# SCH_FG_Command_Controller_2021-10-20.net
KiCad netlist of a schematic drawn in EasyEDA
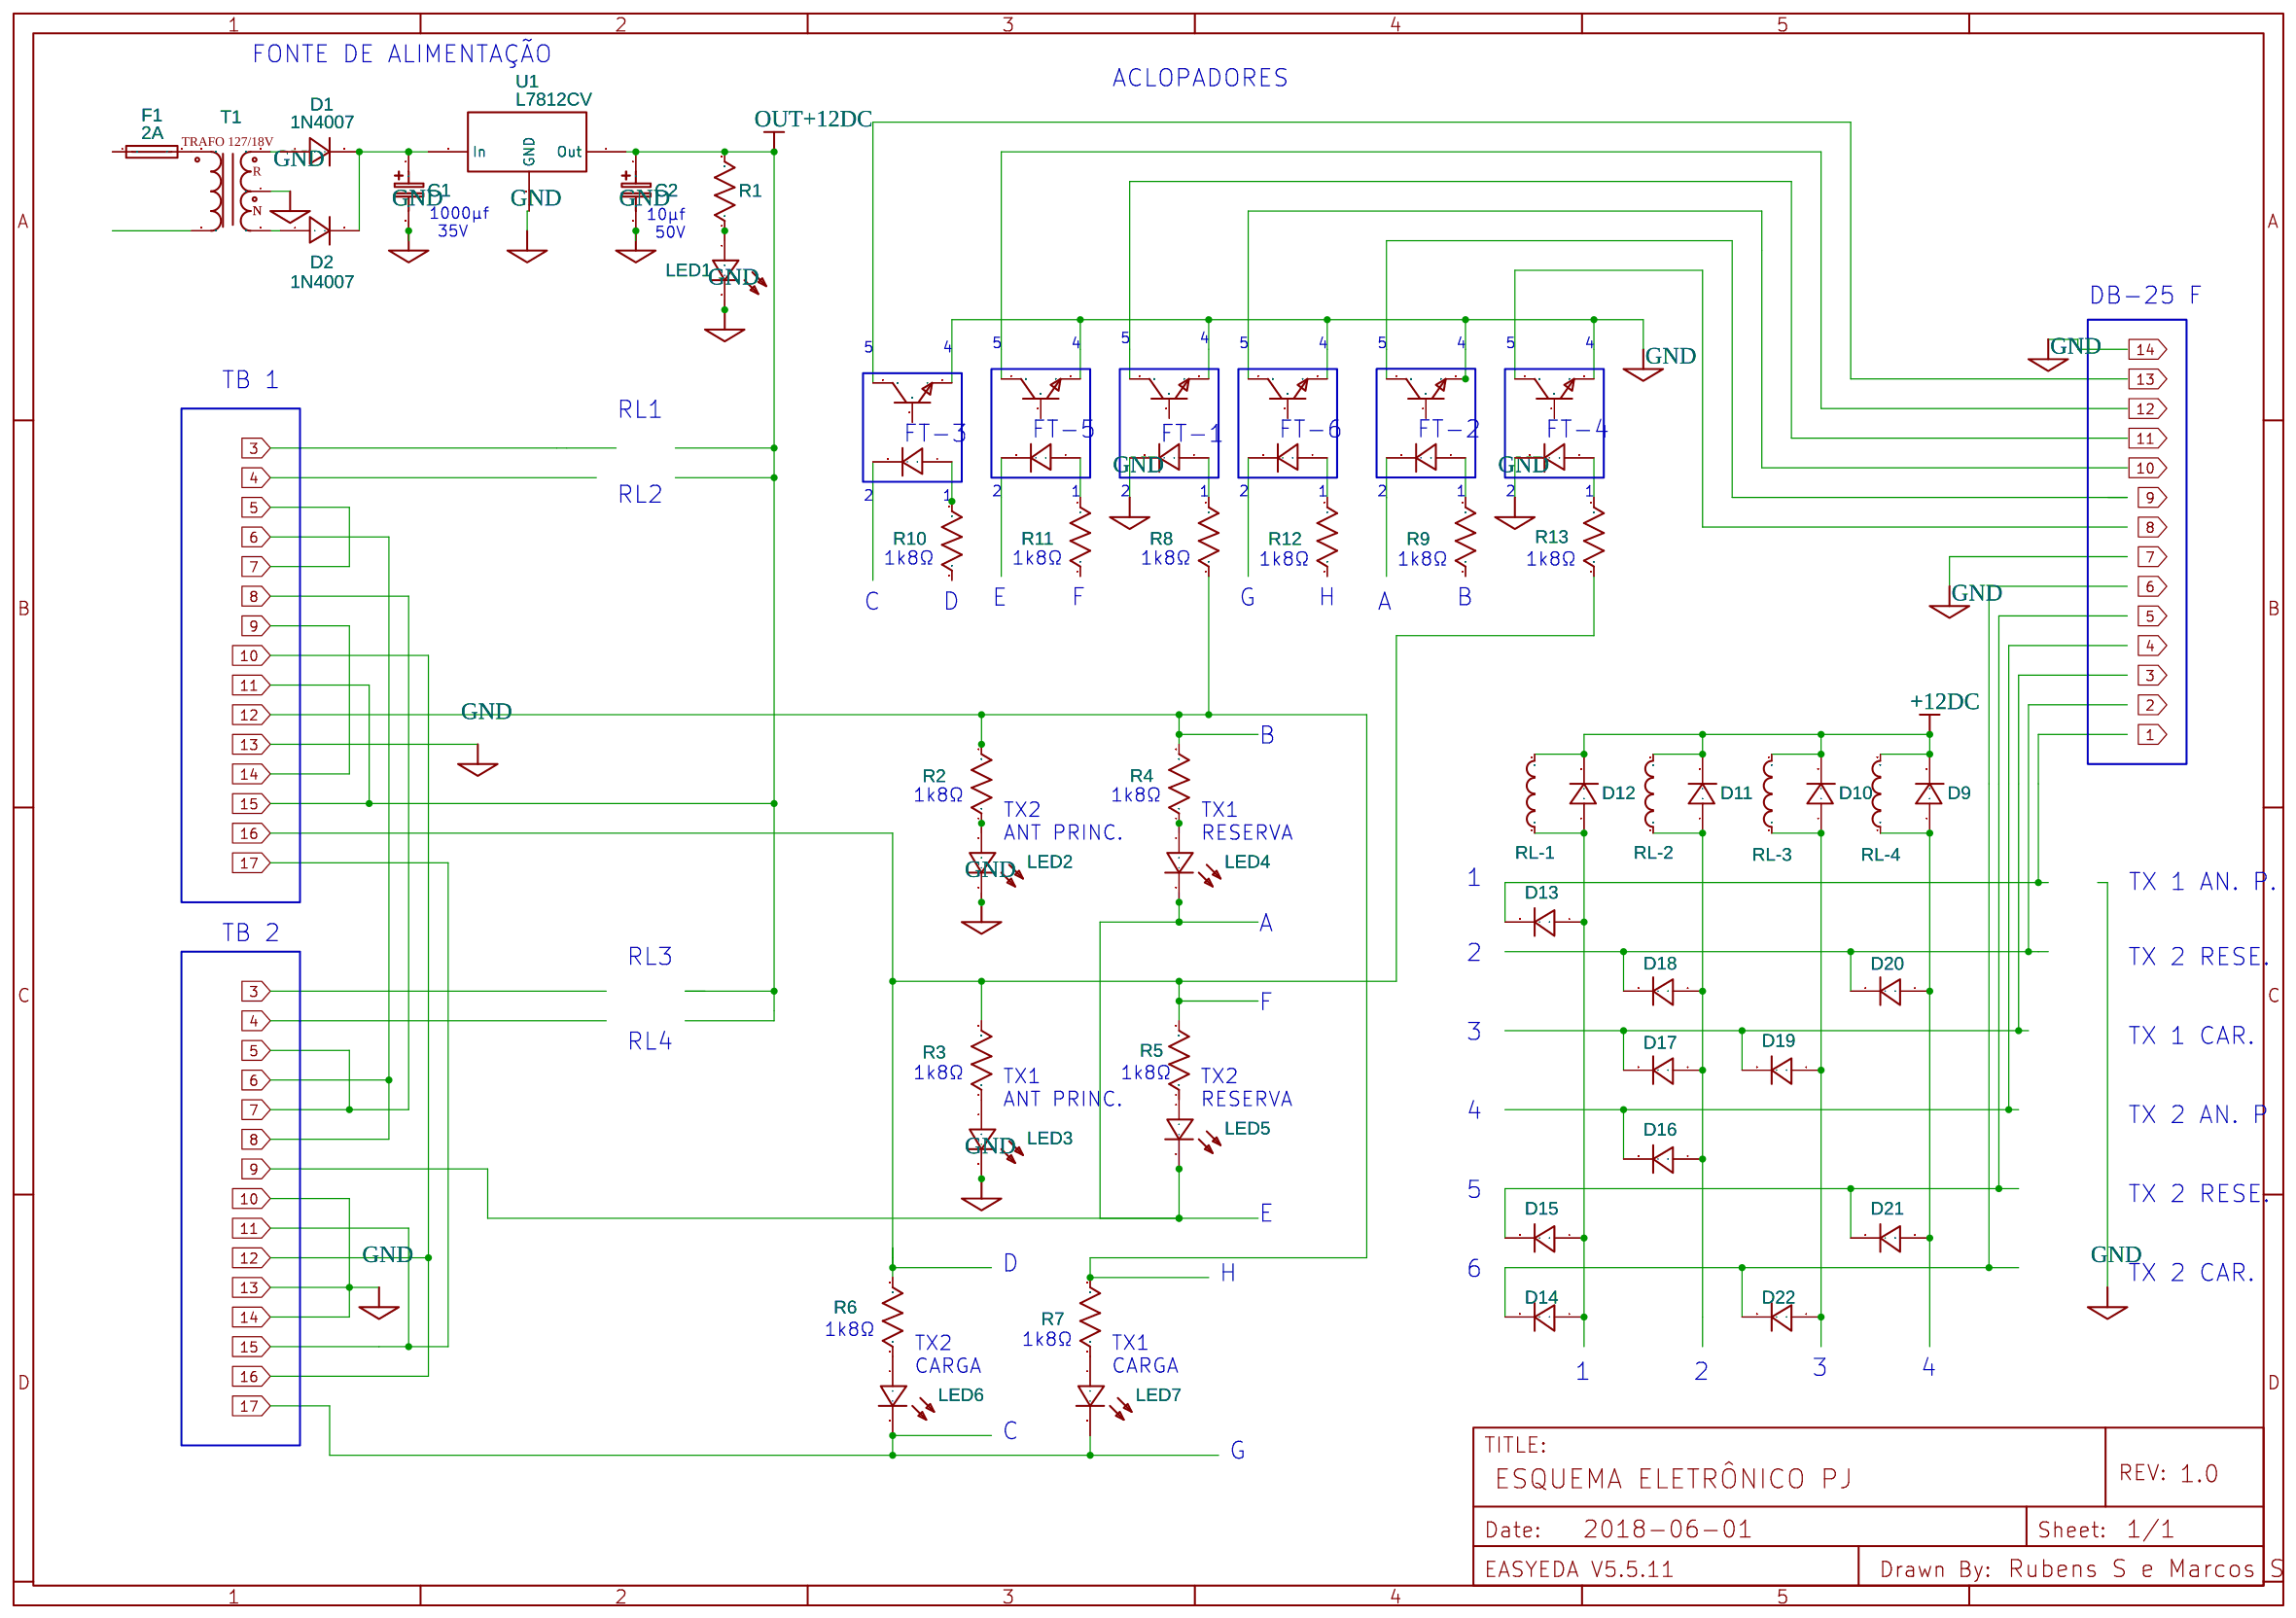
[diagram p0: schematic sheet]

(export (version "E")
  (design (tool "Eeschema 10.0.6"))
  (components
    (comp (ref "6")
      (value "MMBT5551")
      (fields (field (name "BOM_Supplier Part") "C28088"))
      (libsource (lib "") (part "Unknown_715_195"))
    )
    (comp (ref "C1")
      (value "1u")
      (fields (field (name "BOM_Manufacturer Part") "?"))
      (libsource (lib "") (part "Capacitor_1"))
    )
    (comp (ref "C2")
      (value "1u")
      (fields (field (name "BOM_Manufacturer Part") "?"))
      (libsource (lib "") (part "Capacitor"))
    )
    (comp (ref "D1")
      (value "1N4007")
      (fields (field (name "BOM_Manufacturer Part") "?"))
      (libsource (lib "") (part "Unknown_155_70"))
    )
    (comp (ref "D2")
      (value "1N4007")
      (fields (field (name "BOM_Manufacturer Part") "?"))
      (libsource (lib "") (part "Unknown_155_110"))
    )
    (comp (ref "D3")
      (value "1N4148")
      (fields (field (name "BOM_Manufacturer Part") "?"))
      (libsource (lib "") (part "Unknown_645_225"))
    )
    (comp (ref "D4")
      (value "1N4148")
      (fields (field (name "BOM_Manufacturer Part") "?"))
      (libsource (lib "") (part "Unknown_520_225"))
    )
    (comp (ref "D5")
      (value "1N4148")
      (fields (field (name "BOM_Manufacturer Part") "?"))
      (libsource (lib "") (part "Unknown_780_225"))
    )
    (comp (ref "D6")
      (value "1N4148")
      (fields (field (name "BOM_Manufacturer Part") "?"))
      (libsource (lib "") (part "Unknown_455_227"))
    )
    (comp (ref "D7")
      (value "1N4148")
      (fields (field (name "BOM_Manufacturer Part") "?"))
      (libsource (lib "") (part "Unknown_715_225"))
    )
    (comp (ref "D8")
      (value "1N4148")
      (fields (field (name "BOM_Manufacturer Part") "?"))
      (libsource (lib "") (part "Unknown_585_225"))
    )
    (comp (ref "D9")
      (value "1N4148")
      (fields (field (name "BOM_Manufacturer Part") "?"))
      (libsource (lib "") (part "Unknown_970_395"))
    )
    (comp (ref "D10")
      (value "1N4148")
      (fields (field (name "BOM_Manufacturer Part") "?"))
      (libsource (lib "") (part "Unknown_915_395"))
    )
    (comp (ref "D11")
      (value "1N4148")
      (fields (field (name "BOM_Manufacturer Part") "?"))
      (libsource (lib "") (part "Unknown_855_395"))
    )
    (comp (ref "D12")
      (value "1N4148")
      (fields (field (name "BOM_Manufacturer Part") "?"))
      (libsource (lib "") (part "Unknown_795_395"))
    )
    (comp (ref "D13")
      (value "1N4148")
      (fields (field (name "BOM_Manufacturer Part") "?"))
      (libsource (lib "") (part "Unknown_775_460"))
    )
    (comp (ref "D14")
      (value "1N4148")
      (fields (field (name "BOM_Manufacturer Part") "?"))
      (libsource (lib "") (part "Unknown_775_660"))
    )
    (comp (ref "D15")
      (value "1N4148")
      (fields (field (name "BOM_Manufacturer Part") "?"))
      (libsource (lib "") (part "Unknown_775_620"))
    )
    (comp (ref "D16")
      (value "1N4148")
      (fields (field (name "BOM_Manufacturer Part") "?"))
      (libsource (lib "") (part "Unknown_835_580"))
    )
    (comp (ref "D17")
      (value "1N4148")
      (fields (field (name "BOM_Manufacturer Part") "?"))
      (libsource (lib "") (part "Unknown_835_535"))
    )
    (comp (ref "D18")
      (value "1N4148")
      (fields (field (name "BOM_Manufacturer Part") "?"))
      (libsource (lib "") (part "Unknown_835_495"))
    )
    (comp (ref "D19")
      (value "1N4148")
      (fields (field (name "BOM_Manufacturer Part") "?"))
      (libsource (lib "") (part "Unknown_895_535"))
    )
    (comp (ref "D20")
      (value "1N4148")
      (fields (field (name "BOM_Manufacturer Part") "?"))
      (libsource (lib "") (part "Unknown_950_495"))
    )
    (comp (ref "D21")
      (value "1N4148")
      (fields (field (name "BOM_Manufacturer Part") "?"))
      (libsource (lib "") (part "Unknown_950_620"))
    )
    (comp (ref "D22")
      (value "1N4148")
      (fields (field (name "BOM_Manufacturer Part") "?"))
      (libsource (lib "") (part "Unknown_895_660"))
    )
    (comp (ref "F1")
      (value "2A")
      (fields
        (field (name "BOM_Manufacturer Part") "Glass tube fuse2A 3F 250VAC")
        (field (name "BOM_Supplier Part") "C71017")
      )
      (libsource (lib "") (part "Unknown_70_70"))
    )
    (comp (ref "LED1")
      (value "LED 3MM")
      (fields (field (name "BOM_Manufacturer Part") "204-10UYC/S530-A3"))
      (libsource (lib "") (part "Unknown_360_130"))
    )
    (comp (ref "LED2")
      (value "NO")
      (fields (field (name "BOM_Manufacturer Part") "204-10UYC/S530-A3"))
      (libsource (lib "") (part "Unknown_490_430"))
    )
    (comp (ref "LED3")
      (value "LED 3MM")
      (fields (field (name "BOM_Manufacturer Part") "204-10UYC/S530-A3"))
      (libsource (lib "") (part "Unknown_490_570"))
    )
    (comp (ref "LED4")
      (value "LED 3MM")
      (fields (field (name "BOM_Manufacturer Part") "204-10UYC/S530-A3"))
      (libsource (lib "") (part "Unknown_590_430"))
    )
    (comp (ref "LED5")
      (value "LED 3MM")
      (fields (field (name "BOM_Manufacturer Part") "204-10UYC/S530-A3"))
      (libsource (lib "") (part "Unknown_590_565"))
    )
    (comp (ref "LED6")
      (value "LED 3MM")
      (fields (field (name "BOM_Manufacturer Part") "204-10UYC/S530-A3"))
      (libsource (lib "") (part "Unknown_445_700"))
    )
    (comp (ref "LED7")
      (value "LED 3MM")
      (fields (field (name "BOM_Manufacturer Part") "204-10UYC/S530-A3"))
      (libsource (lib "") (part "Unknown_545_700"))
    )
    (comp (ref "Q1")
      (value "MMBT5551")
      (fields (field (name "BOM_Supplier Part") "C28088"))
      (libsource (lib "") (part "Unknown_585_195"))
    )
    (comp (ref "Q3")
      (value "MMBT5551")
      (fields (field (name "BOM_Supplier Part") "C28088"))
      (libsource (lib "") (part "Unknown_455_197"))
    )
    (comp (ref "Q4")
      (value "MMBT5551")
      (fields (field (name "BOM_Supplier Part") "C28088"))
      (libsource (lib "") (part "Unknown_780_195"))
    )
    (comp (ref "Q5")
      (value "MMBT5551")
      (fields (field (name "BOM_Supplier Part") "C28088"))
      (libsource (lib "") (part "Unknown_520_195"))
    )
    (comp (ref "Q6")
      (value "MMBT5551")
      (fields (field (name "BOM_Supplier Part") "C28088"))
      (libsource (lib "") (part "Unknown_645_195"))
    )
    (comp (ref "R1")
      (value "1k")
      (fields (field (name "BOM_Manufacturer Part") "?"))
      (libsource (lib "") (part "Res_AXIAL-0.3(1/8W)_US"))
    )
    (comp (ref "R2")
      (value "1k")
      (fields (field (name "BOM_Manufacturer Part") "?"))
      (libsource (lib "") (part "Res_AXIAL-0.3(1/8W)_US"))
    )
    (comp (ref "R3")
      (value "1k")
      (fields (field (name "BOM_Manufacturer Part") "?"))
      (libsource (lib "") (part "Res_AXIAL-0.3(1/8W)_US"))
    )
    (comp (ref "R4")
      (value "1k")
      (fields (field (name "BOM_Manufacturer Part") "?"))
      (libsource (lib "") (part "Res_AXIAL-0.3(1/8W)_US"))
    )
    (comp (ref "R5")
      (value "1k")
      (fields (field (name "BOM_Manufacturer Part") "?"))
      (libsource (lib "") (part "Res_AXIAL-0.3(1/8W)_US"))
    )
    (comp (ref "R6")
      (value "1k")
      (fields (field (name "BOM_Manufacturer Part") "?"))
      (libsource (lib "") (part "Res_AXIAL-0.3(1/8W)_US"))
    )
    (comp (ref "R7")
      (value "1k")
      (fields (field (name "BOM_Manufacturer Part") "?"))
      (libsource (lib "") (part "Res_AXIAL-0.3(1/8W)_US"))
    )
    (comp (ref "R8")
      (value "1k")
      (fields (field (name "BOM_Manufacturer Part") "?"))
      (libsource (lib "") (part "Res_AXIAL-0.3(1/8W)_US"))
    )
    (comp (ref "R9")
      (value "1k")
      (fields (field (name "BOM_Manufacturer Part") "?"))
      (libsource (lib "") (part "Res_AXIAL-0.3(1/8W)_US"))
    )
    (comp (ref "R10")
      (value "1k")
      (fields (field (name "BOM_Manufacturer Part") "?"))
      (libsource (lib "") (part "Res_AXIAL-0.3(1/8W)_US"))
    )
    (comp (ref "R11")
      (value "1k")
      (fields (field (name "BOM_Manufacturer Part") "?"))
      (libsource (lib "") (part "Res_AXIAL-0.3(1/8W)_US"))
    )
    (comp (ref "R12")
      (value "1k")
      (fields (field (name "BOM_Manufacturer Part") "?"))
      (libsource (lib "") (part "Res_AXIAL-0.3(1/8W)_US"))
    )
    (comp (ref "R13")
      (value "1k")
      (fields (field (name "BOM_Manufacturer Part") "?"))
      (libsource (lib "") (part "Res_AXIAL-0.3(1/8W)_US"))
    )
    (comp (ref "RL-1")
      (value "1m")
      (fields (field (name "BOM_Manufacturer Part") "?"))
      (libsource (lib "") (part "Inductor"))
    )
    (comp (ref "RL-2")
      (value "1m")
      (fields (field (name "BOM_Manufacturer Part") "?"))
      (libsource (lib "") (part "Inductor"))
    )
    (comp (ref "RL-3")
      (value "1m")
      (fields (field (name "BOM_Manufacturer Part") "?"))
      (libsource (lib "") (part "Inductor"))
    )
    (comp (ref "RL-4")
      (value "1m")
      (fields (field (name "BOM_Manufacturer Part") "?"))
      (libsource (lib "") (part "Inductor"))
    )
    (comp (ref "T1")
      (value "XFMR_TAP")
      (fields (field (name "BOM_Manufacturer Part") "?"))
      (libsource (lib "") (part "Unknown_110_90"))
    )
    (comp (ref "U1")
      (value "L7812CV")
      (fields (field (name "BOM_Manufacturer Part") "AMS1117-3.3") (field (name "BOM_Supplier Part") "C6186"))
      (libsource (lib "") (part "Unknown_260_70"))
    )
  )
  (nets
    (net (code "1") (name "+12DC") (class "Default")
      (node (ref "D10") (pin "2") (pinfunction "-_2") (pintype "unspecified"))
      (node (ref "D11") (pin "2") (pinfunction "-_2") (pintype "unspecified"))
      (node (ref "D12") (pin "2") (pinfunction "-_2") (pintype "unspecified"))
      (node (ref "D9") (pin "2") (pinfunction "-_2") (pintype "unspecified"))
      (node (ref "RL-1") (pin "2") (pinfunction "2_2") (pintype "unspecified"))
      (node (ref "RL-2") (pin "2") (pinfunction "2_2") (pintype "unspecified"))
      (node (ref "RL-3") (pin "2") (pinfunction "2_2") (pintype "unspecified"))
      (node (ref "RL-4") (pin "2") (pinfunction "2_2") (pintype "unspecified"))
    )
    (net (code "7") (name "10") (class "Default")
      (node (ref "6") (pin "3") (pinfunction "E_3") (pintype "unspecified"))
      (node (ref "C1") (pin "2") (pinfunction "2_2") (pintype "unspecified"))
      (node (ref "C2") (pin "2") (pinfunction "2_2") (pintype "unspecified"))
      (node (ref "D5") (pin "2") (pinfunction "-_2") (pintype "unspecified"))
      (node (ref "D8") (pin "2") (pinfunction "-_2") (pintype "unspecified"))
      (node (ref "LED1") (pin "2") (pinfunction "-_2") (pintype "unspecified"))
      (node (ref "LED2") (pin "2") (pinfunction "-_2") (pintype "unspecified"))
      (node (ref "LED3") (pin "2") (pinfunction "-_2") (pintype "unspecified"))
      (node (ref "LED4") (pin "2") (pinfunction "-_2") (pintype "unspecified"))
      (node (ref "LED5") (pin "2") (pinfunction "-_2") (pintype "unspecified"))
      (node (ref "Q1") (pin "3") (pinfunction "E_3") (pintype "unspecified"))
      (node (ref "Q3") (pin "3") (pinfunction "E_3") (pintype "unspecified"))
      (node (ref "Q4") (pin "3") (pinfunction "E_3") (pintype "unspecified"))
      (node (ref "Q5") (pin "3") (pinfunction "E_3") (pintype "unspecified"))
      (node (ref "Q6") (pin "3") (pinfunction "E_3") (pintype "unspecified"))
      (node (ref "R13") (pin "1") (pinfunction "1_1") (pintype "unspecified"))
      (node (ref "R2") (pin "2") (pinfunction "2_2") (pintype "unspecified"))
      (node (ref "R3") (pin "2") (pinfunction "2_2") (pintype "unspecified"))
      (node (ref "R4") (pin "2") (pinfunction "2_2") (pintype "unspecified"))
      (node (ref "R5") (pin "2") (pinfunction "2_2") (pintype "unspecified"))
      (node (ref "R6") (pin "2") (pinfunction "2_2") (pintype "unspecified"))
      (node (ref "R7") (pin "2") (pinfunction "2_2") (pintype "unspecified"))
      (node (ref "R8") (pin "1") (pinfunction "1_1") (pintype "unspecified"))
      (node (ref "T1") (pin "4") (pinfunction "4_4") (pintype "unspecified"))
      (node (ref "U1") (pin "1") (pinfunction "GND_1") (pintype "unspecified"))
    )
    (net (code "8") (name "11") (class "Default")
      (node (ref "C2") (pin "1") (pinfunction "1_1") (pintype "unspecified"))
      (node (ref "LED6") (pin "2") (pinfunction "-_2") (pintype "unspecified"))
      (node (ref "LED7") (pin "2") (pinfunction "-_2") (pintype "unspecified"))
      (node (ref "R1") (pin "2") (pinfunction "2_2") (pintype "unspecified"))
      (node (ref "U1") (pin "2") (pinfunction "Out_2") (pintype "unspecified"))
    )
    (net (code "9") (name "Net-(D1-+)") (class "Default")
      (node (ref "D1") (pin "1") (pinfunction "+_1") (pintype "unspecified"))
      (node (ref "T1") (pin "5") (pinfunction "5_5") (pintype "unspecified"))
    )
    (net (code "10") (name "Net-(D1--)") (class "Default")
      (node (ref "C1") (pin "1") (pinfunction "1_1") (pintype "unspecified"))
      (node (ref "D1") (pin "2") (pinfunction "-_2") (pintype "unspecified"))
      (node (ref "D2") (pin "2") (pinfunction "-_2") (pintype "unspecified"))
      (node (ref "U1") (pin "3") (pinfunction "In_3") (pintype "unspecified"))
    )
    (net (code "11") (name "Net-(D2-+)") (class "Default")
      (node (ref "D2") (pin "1") (pinfunction "+_1") (pintype "unspecified"))
      (node (ref "T1") (pin "3") (pinfunction "3_3") (pintype "unspecified"))
    )
    (net (code "12") (name "Net-(D3-+)") (class "Default")
      (node (ref "D3") (pin "1") (pinfunction "+_1") (pintype "unspecified"))
      (node (ref "R12") (pin "2") (pinfunction "2_2") (pintype "unspecified"))
    )
    (net (code "13") (name "Net-(D4-+)") (class "Default")
      (node (ref "D4") (pin "1") (pinfunction "+_1") (pintype "unspecified"))
      (node (ref "R11") (pin "2") (pinfunction "2_2") (pintype "unspecified"))
    )
    (net (code "14") (name "Net-(D5-+)") (class "Default")
      (node (ref "D5") (pin "1") (pinfunction "+_1") (pintype "unspecified"))
      (node (ref "R13") (pin "2") (pinfunction "2_2") (pintype "unspecified"))
    )
    (net (code "15") (name "Net-(D6-+)") (class "Default")
      (node (ref "D6") (pin "1") (pinfunction "+_1") (pintype "unspecified"))
      (node (ref "R10") (pin "2") (pinfunction "2_2") (pintype "unspecified"))
    )
    (net (code "16") (name "Net-(D7-+)") (class "Default")
      (node (ref "D7") (pin "1") (pinfunction "+_1") (pintype "unspecified"))
      (node (ref "R9") (pin "2") (pinfunction "2_2") (pintype "unspecified"))
    )
    (net (code "17") (name "Net-(D8-+)") (class "Default")
      (node (ref "D8") (pin "1") (pinfunction "+_1") (pintype "unspecified"))
      (node (ref "R8") (pin "2") (pinfunction "2_2") (pintype "unspecified"))
    )
    (net (code "18") (name "Net-(D10-+)") (class "Default")
      (node (ref "D10") (pin "1") (pinfunction "+_1") (pintype "unspecified"))
      (node (ref "D19") (pin "1") (pinfunction "+_1") (pintype "unspecified"))
      (node (ref "D22") (pin "1") (pinfunction "+_1") (pintype "unspecified"))
      (node (ref "RL-3") (pin "1") (pinfunction "1_1") (pintype "unspecified"))
    )
    (net (code "19") (name "Net-(D11-+)") (class "Default")
      (node (ref "D11") (pin "1") (pinfunction "+_1") (pintype "unspecified"))
      (node (ref "D16") (pin "1") (pinfunction "+_1") (pintype "unspecified"))
      (node (ref "D17") (pin "1") (pinfunction "+_1") (pintype "unspecified"))
      (node (ref "D18") (pin "1") (pinfunction "+_1") (pintype "unspecified"))
      (node (ref "RL-2") (pin "1") (pinfunction "1_1") (pintype "unspecified"))
    )
    (net (code "20") (name "Net-(D12-+)") (class "Default")
      (node (ref "D12") (pin "1") (pinfunction "+_1") (pintype "unspecified"))
      (node (ref "D13") (pin "1") (pinfunction "+_1") (pintype "unspecified"))
      (node (ref "D14") (pin "1") (pinfunction "+_1") (pintype "unspecified"))
      (node (ref "D15") (pin "1") (pinfunction "+_1") (pintype "unspecified"))
      (node (ref "RL-1") (pin "1") (pinfunction "1_1") (pintype "unspecified"))
    )
    (net (code "21") (name "Net-(D14--)") (class "Default")
      (node (ref "D14") (pin "2") (pinfunction "-_2") (pintype "unspecified"))
      (node (ref "D22") (pin "2") (pinfunction "-_2") (pintype "unspecified"))
    )
    (net (code "22") (name "Net-(D15--)") (class "Default")
      (node (ref "D15") (pin "2") (pinfunction "-_2") (pintype "unspecified"))
      (node (ref "D21") (pin "2") (pinfunction "-_2") (pintype "unspecified"))
    )
    (net (code "23") (name "Net-(D17--)") (class "Default")
      (node (ref "D17") (pin "2") (pinfunction "-_2") (pintype "unspecified"))
      (node (ref "D19") (pin "2") (pinfunction "-_2") (pintype "unspecified"))
    )
    (net (code "24") (name "Net-(D18--)") (class "Default")
      (node (ref "D18") (pin "2") (pinfunction "-_2") (pintype "unspecified"))
      (node (ref "D20") (pin "2") (pinfunction "-_2") (pintype "unspecified"))
    )
    (net (code "25") (name "Net-(D20-+)") (class "Default")
      (node (ref "D20") (pin "1") (pinfunction "+_1") (pintype "unspecified"))
      (node (ref "D21") (pin "1") (pinfunction "+_1") (pintype "unspecified"))
      (node (ref "D9") (pin "1") (pinfunction "+_1") (pintype "unspecified"))
      (node (ref "RL-4") (pin "1") (pinfunction "1_1") (pintype "unspecified"))
    )
    (net (code "26") (name "Net-(F1-Pad2)") (class "Default")
      (node (ref "F1") (pin "2") (pinfunction "2_2") (pintype "unspecified"))
      (node (ref "T1") (pin "1") (pinfunction "1_1") (pintype "unspecified"))
    )
    (net (code "27") (name "Net-(LED1-+)") (class "Default")
      (node (ref "LED1") (pin "1") (pinfunction "+_1") (pintype "unspecified"))
      (node (ref "R1") (pin "1") (pinfunction "1_1") (pintype "unspecified"))
    )
    (net (code "28") (name "Net-(LED2-+)") (class "Default")
      (node (ref "LED2") (pin "1") (pinfunction "+_1") (pintype "unspecified"))
      (node (ref "R2") (pin "1") (pinfunction "1_1") (pintype "unspecified"))
    )
    (net (code "29") (name "Net-(LED3-+)") (class "Default")
      (node (ref "LED3") (pin "1") (pinfunction "+_1") (pintype "unspecified"))
      (node (ref "R3") (pin "1") (pinfunction "1_1") (pintype "unspecified"))
    )
    (net (code "30") (name "Net-(LED4-+)") (class "Default")
      (node (ref "LED4") (pin "1") (pinfunction "+_1") (pintype "unspecified"))
      (node (ref "R4") (pin "1") (pinfunction "1_1") (pintype "unspecified"))
    )
    (net (code "31") (name "Net-(LED5-+)") (class "Default")
      (node (ref "LED5") (pin "1") (pinfunction "+_1") (pintype "unspecified"))
      (node (ref "R5") (pin "1") (pinfunction "1_1") (pintype "unspecified"))
    )
    (net (code "32") (name "Net-(LED6-+)") (class "Default")
      (node (ref "LED6") (pin "1") (pinfunction "+_1") (pintype "unspecified"))
      (node (ref "R6") (pin "1") (pinfunction "1_1") (pintype "unspecified"))
    )
    (net (code "33") (name "Net-(LED7-+)") (class "Default")
      (node (ref "LED7") (pin "1") (pinfunction "+_1") (pintype "unspecified"))
      (node (ref "R7") (pin "1") (pinfunction "1_1") (pintype "unspecified"))
    )
    (net (code "34") (name "unconnected-(6-B-Pad1)") (class "Default")
      (node (ref "6") (pin "1") (pinfunction "B_1") (pintype "unspecified"))
    )
    (net (code "35") (name "unconnected-(6-C-Pad2)") (class "Default")
      (node (ref "6") (pin "2") (pinfunction "C_2") (pintype "unspecified"))
    )
    (net (code "36") (name "unconnected-(D3---Pad2)") (class "Default")
      (node (ref "D3") (pin "2") (pinfunction "-_2") (pintype "unspecified"))
    )
    (net (code "37") (name "unconnected-(D4---Pad2)") (class "Default")
      (node (ref "D4") (pin "2") (pinfunction "-_2") (pintype "unspecified"))
    )
    (net (code "38") (name "unconnected-(D6---Pad2)") (class "Default")
      (node (ref "D6") (pin "2") (pinfunction "-_2") (pintype "unspecified"))
    )
    (net (code "39") (name "unconnected-(D7---Pad2)") (class "Default")
      (node (ref "D7") (pin "2") (pinfunction "-_2") (pintype "unspecified"))
    )
    (net (code "40") (name "unconnected-(D13---Pad2)") (class "Default")
      (node (ref "D13") (pin "2") (pinfunction "-_2") (pintype "unspecified"))
    )
    (net (code "41") (name "unconnected-(D16---Pad2)") (class "Default")
      (node (ref "D16") (pin "2") (pinfunction "-_2") (pintype "unspecified"))
    )
    (net (code "42") (name "unconnected-(F1-Pad1)") (class "Default")
      (node (ref "F1") (pin "1") (pinfunction "1_1") (pintype "unspecified"))
    )
    (net (code "43") (name "unconnected-(Q1-B-Pad1)") (class "Default")
      (node (ref "Q1") (pin "1") (pinfunction "B_1") (pintype "unspecified"))
    )
    (net (code "44") (name "unconnected-(Q1-C-Pad2)") (class "Default")
      (node (ref "Q1") (pin "2") (pinfunction "C_2") (pintype "unspecified"))
    )
    (net (code "45") (name "unconnected-(Q3-B-Pad1)") (class "Default")
      (node (ref "Q3") (pin "1") (pinfunction "B_1") (pintype "unspecified"))
    )
    (net (code "46") (name "unconnected-(Q3-C-Pad2)") (class "Default")
      (node (ref "Q3") (pin "2") (pinfunction "C_2") (pintype "unspecified"))
    )
    (net (code "47") (name "unconnected-(Q4-B-Pad1)") (class "Default")
      (node (ref "Q4") (pin "1") (pinfunction "B_1") (pintype "unspecified"))
    )
    (net (code "48") (name "unconnected-(Q4-C-Pad2)") (class "Default")
      (node (ref "Q4") (pin "2") (pinfunction "C_2") (pintype "unspecified"))
    )
    (net (code "49") (name "unconnected-(Q5-B-Pad1)") (class "Default")
      (node (ref "Q5") (pin "1") (pinfunction "B_1") (pintype "unspecified"))
    )
    (net (code "50") (name "unconnected-(Q5-C-Pad2)") (class "Default")
      (node (ref "Q5") (pin "2") (pinfunction "C_2") (pintype "unspecified"))
    )
    (net (code "51") (name "unconnected-(Q6-B-Pad1)") (class "Default")
      (node (ref "Q6") (pin "1") (pinfunction "B_1") (pintype "unspecified"))
    )
    (net (code "52") (name "unconnected-(Q6-C-Pad2)") (class "Default")
      (node (ref "Q6") (pin "2") (pinfunction "C_2") (pintype "unspecified"))
    )
    (net (code "53") (name "unconnected-(R9-Pad1)") (class "Default")
      (node (ref "R9") (pin "1") (pinfunction "1_1") (pintype "unspecified"))
    )
    (net (code "54") (name "unconnected-(R10-Pad1)") (class "Default")
      (node (ref "R10") (pin "1") (pinfunction "1_1") (pintype "unspecified"))
    )
    (net (code "55") (name "unconnected-(R11-Pad1)") (class "Default")
      (node (ref "R11") (pin "1") (pinfunction "1_1") (pintype "unspecified"))
    )
    (net (code "56") (name "unconnected-(R12-Pad1)") (class "Default")
      (node (ref "R12") (pin "1") (pinfunction "1_1") (pintype "unspecified"))
    )
    (net (code "57") (name "unconnected-(T1-Pad2)") (class "Default")
      (node (ref "T1") (pin "2") (pinfunction "2_2") (pintype "unspecified"))
    )
  )
)
